# 10AmpBuckV3.net
KiCad netlist of a schematic drawn in EAGLE
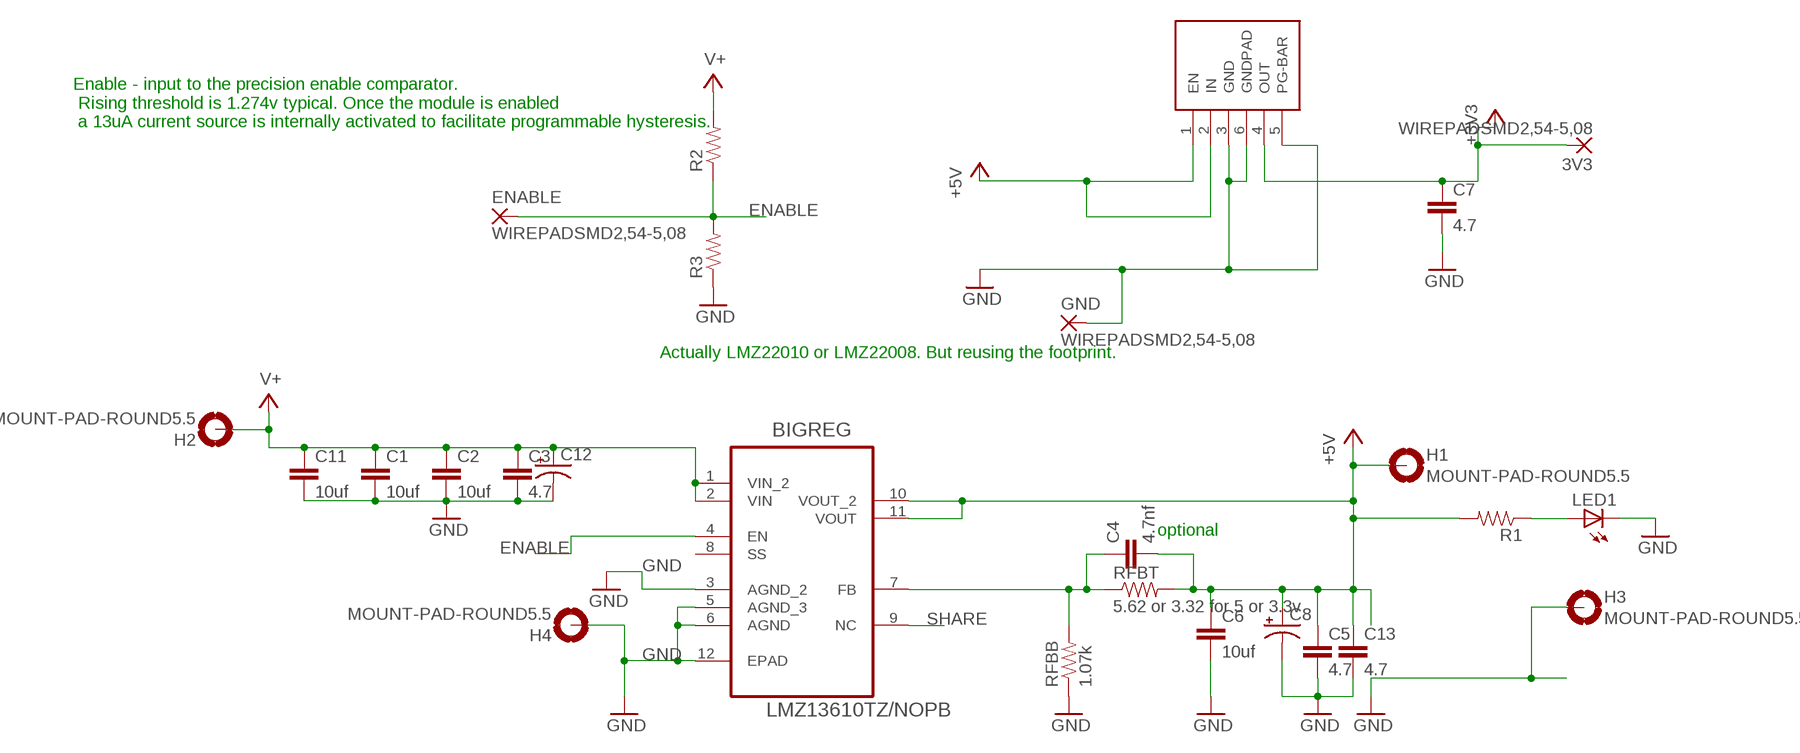
[diagram p0: schematic, sheet 1]

(export (version "E")
  (design (tool "Eeschema 10.0.6"))
  (components
    (comp (ref "3V3")
      (value "WIREPADSMD2,54-5,08")
      (footprint "eagle-import:SMD2,54-5,08")
      (libsource (lib "eagle-import") (part "WIREPADSMD2,54-5,08"))
    )
    (comp (ref "BIGREG")
      (value "LMZ13610TZ/NOPB")
      (footprint "eagle-import:TI_TO-PMOD-11")
      (libsource (lib "eagle-import") (part "LMZ13610TZ/NOPB"))
    )
    (comp (ref "C1")
      (value "10uf")
      (footprint "eagle-import:1206")
      (libsource (lib "eagle-import") (part "CAP1206"))
    )
    (comp (ref "C2")
      (value "10uf")
      (footprint "eagle-import:1206")
      (libsource (lib "eagle-import") (part "CAP1206"))
    )
    (comp (ref "C3")
      (value "4.7")
      (footprint "eagle-import:1206")
      (libsource (lib "eagle-import") (part "CAP1206"))
    )
    (comp (ref "C4")
      (value "4.7nf")
      (footprint "eagle-import:0603-CAP")
      (libsource (lib "eagle-import") (part "SparkFun-Passives_CAP0603-CAP"))
    )
    (comp (ref "C5")
      (value "4.7")
      (footprint "eagle-import:1206")
      (libsource (lib "eagle-import") (part "CAP1206"))
    )
    (comp (ref "C6")
      (value "10uf")
      (footprint "eagle-import:1206")
      (libsource (lib "eagle-import") (part "CAP1206"))
    )
    (comp (ref "C7")
      (value "4.7")
      (footprint "eagle-import:1206")
      (libsource (lib "eagle-import") (part "CAP1206"))
    )
    (comp (ref "C8")
      (value "CAP_POLPTH1")
      (footprint "eagle-import:CPOL-RADIAL-100UF-25V")
      (libsource (lib "eagle-import") (part "CAP_POLPTH1"))
    )
    (comp (ref "C11")
      (value "10uf")
      (footprint "eagle-import:1206")
      (libsource (lib "eagle-import") (part "CAP1206"))
    )
    (comp (ref "C12")
      (value "CAP_POLPTH1")
      (footprint "eagle-import:CPOL-RADIAL-100UF-25V")
      (libsource (lib "eagle-import") (part "CAP_POLPTH1"))
    )
    (comp (ref "C13")
      (value "4.7")
      (footprint "eagle-import:1206")
      (libsource (lib "eagle-import") (part "CAP1206"))
    )
    (comp (ref "ENABLE")
      (value "WIREPADSMD2,54-5,08")
      (footprint "eagle-import:SMD2,54-5,08")
      (libsource (lib "eagle-import") (part "WIREPADSMD2,54-5,08"))
    )
    (comp (ref "GND")
      (value "WIREPADSMD2,54-5,08")
      (footprint "eagle-import:SMD2,54-5,08")
      (libsource (lib "eagle-import") (part "WIREPADSMD2,54-5,08"))
    )
    (comp (ref "H1")
      (value "MOUNT-PAD-ROUND5.5")
      (footprint "eagle-import:5,5-PAD")
      (libsource (lib "eagle-import") (part "MOUNT-PAD-ROUND5.5"))
    )
    (comp (ref "H2")
      (value "MOUNT-PAD-ROUND5.5")
      (footprint "eagle-import:5,5-PAD")
      (libsource (lib "eagle-import") (part "MOUNT-PAD-ROUND5.5"))
    )
    (comp (ref "H3")
      (value "MOUNT-PAD-ROUND5.5")
      (footprint "eagle-import:5,5-PAD")
      (libsource (lib "eagle-import") (part "MOUNT-PAD-ROUND5.5"))
    )
    (comp (ref "H4")
      (value "MOUNT-PAD-ROUND5.5")
      (footprint "eagle-import:5,5-PAD")
      (libsource (lib "eagle-import") (part "MOUNT-PAD-ROUND5.5"))
    )
    (comp (ref "LED1")
      (value "LED1206")
      (footprint "eagle-import:LED-1206")
      (libsource (lib "eagle-import") (part "LED1206"))
    )
    (comp (ref "R1")
      (value "RESISTOR0603-RES")
      (footprint "eagle-import:0603-RES")
      (libsource (lib "eagle-import") (part "RESISTOR0603-RES"))
    )
    (comp (ref "R2")
      (value "RESISTOR0603-RES")
      (footprint "eagle-import:0603-RES")
      (libsource (lib "eagle-import") (part "RESISTOR0603-RES"))
    )
    (comp (ref "R3")
      (value "RESISTOR0603-RES")
      (footprint "eagle-import:0603-RES")
      (libsource (lib "eagle-import") (part "RESISTOR0603-RES"))
    )
    (comp (ref "RFBB")
      (value "1.07k")
      (footprint "eagle-import:0603-RES")
      (libsource (lib "eagle-import") (part "RESISTOR0603"))
    )
    (comp (ref "RFBT")
      (value "5.62 or 3.32 for 5 or 3.3v")
      (footprint "eagle-import:0603-RES")
      (libsource (lib "eagle-import") (part "RESISTOR0603"))
    )
    (comp (ref "U$1")
      (value "TPS75533")
      (footprint "eagle-import:TO263-5")
      (libsource (lib "eagle-import") (part "TPS75533"))
    )
  )
  (nets
    (net (code "1") (name "+3V3") (class "Default")
      (node (ref "3V3") (pin "1") (pinfunction "P_1") (pintype "passive"))
      (node (ref "C7") (pin "1") (pinfunction "1_1") (pintype "passive"))
      (node (ref "U$1") (pin "4") (pinfunction "OUT_4") (pintype "bidirectional"))
    )
    (net (code "2") (name "+5V") (class "Default")
      (node (ref "BIGREG") (pin "10") (pinfunction "VOUT_2_10") (pintype "output"))
      (node (ref "BIGREG") (pin "11") (pinfunction "VOUT_11") (pintype "output"))
      (node (ref "C13") (pin "1") (pinfunction "1_1") (pintype "passive"))
      (node (ref "C4") (pin "2") (pinfunction "2_2") (pintype "passive"))
      (node (ref "C5") (pin "1") (pinfunction "1_1") (pintype "passive"))
      (node (ref "C6") (pin "1") (pinfunction "1_1") (pintype "passive"))
      (node (ref "C8") (pin "1") (pinfunction "+_1") (pintype "passive"))
      (node (ref "H1") (pin "B5,5") (pinfunction "MOUNT_B5,5") (pintype "passive"))
      (node (ref "R1") (pin "2") (pinfunction "2_2") (pintype "passive"))
      (node (ref "RFBT") (pin "2") (pinfunction "2_2") (pintype "passive"))
      (node (ref "U$1") (pin "1") (pinfunction "EN_1") (pintype "bidirectional"))
      (node (ref "U$1") (pin "2") (pinfunction "IN_2") (pintype "bidirectional"))
    )
    (net (code "3") (name "/ENABLE") (class "Default")
      (node (ref "BIGREG") (pin "4") (pinfunction "EN_4") (pintype "input"))
      (node (ref "ENABLE") (pin "1") (pinfunction "P_1") (pintype "passive"))
      (node (ref "R2") (pin "1") (pinfunction "1_1") (pintype "passive"))
      (node (ref "R3") (pin "2") (pinfunction "2_2") (pintype "passive"))
    )
    (net (code "5") (name "GND") (class "Default")
      (node (ref "BIGREG") (pin "12") (pinfunction "EPAD_12") (pintype "passive"))
      (node (ref "BIGREG") (pin "3") (pinfunction "AGND_2_3") (pintype "passive"))
      (node (ref "BIGREG") (pin "5") (pinfunction "AGND_3_5") (pintype "passive"))
      (node (ref "BIGREG") (pin "6") (pinfunction "AGND_6") (pintype "passive"))
      (node (ref "C1") (pin "2") (pinfunction "2_2") (pintype "passive"))
      (node (ref "C11") (pin "2") (pinfunction "2_2") (pintype "passive"))
      (node (ref "C12") (pin "2") (pinfunction "-_2") (pintype "passive"))
      (node (ref "C13") (pin "2") (pinfunction "2_2") (pintype "passive"))
      (node (ref "C2") (pin "2") (pinfunction "2_2") (pintype "passive"))
      (node (ref "C3") (pin "2") (pinfunction "2_2") (pintype "passive"))
      (node (ref "C5") (pin "2") (pinfunction "2_2") (pintype "passive"))
      (node (ref "C6") (pin "2") (pinfunction "2_2") (pintype "passive"))
      (node (ref "C7") (pin "2") (pinfunction "2_2") (pintype "passive"))
      (node (ref "C8") (pin "2") (pinfunction "-_2") (pintype "passive"))
      (node (ref "GND") (pin "1") (pinfunction "P_1") (pintype "passive"))
      (node (ref "H3") (pin "B5,5") (pinfunction "MOUNT_B5,5") (pintype "passive"))
      (node (ref "H4") (pin "B5,5") (pinfunction "MOUNT_B5,5") (pintype "passive"))
      (node (ref "LED1") (pin "C") (pinfunction "C_C") (pintype "passive"))
      (node (ref "R3") (pin "1") (pinfunction "1_1") (pintype "passive"))
      (node (ref "RFBB") (pin "1") (pinfunction "1_1") (pintype "passive"))
      (node (ref "U$1") (pin "3") (pinfunction "GND_3") (pintype "bidirectional"))
      (node (ref "U$1") (pin "5") (pinfunction "PG-BAR_5") (pintype "bidirectional"))
      (node (ref "U$1") (pin "6") (pinfunction "GNDPAD_6") (pintype "bidirectional"))
    )
    (net (code "6") (name "Net-(BIGREG-FB)") (class "Default")
      (node (ref "BIGREG") (pin "7") (pinfunction "FB_7") (pintype "input"))
      (node (ref "C4") (pin "1") (pinfunction "1_1") (pintype "passive"))
      (node (ref "RFBB") (pin "2") (pinfunction "2_2") (pintype "passive"))
      (node (ref "RFBT") (pin "1") (pinfunction "1_1") (pintype "passive"))
    )
    (net (code "7") (name "Net-(LED1-PadA)") (class "Default")
      (node (ref "LED1") (pin "A") (pinfunction "A_A") (pintype "passive"))
      (node (ref "R1") (pin "1") (pinfunction "1_1") (pintype "passive"))
    )
    (net (code "8") (name "V+") (class "Default")
      (node (ref "BIGREG") (pin "1") (pinfunction "VIN_2_1") (pintype "power_in"))
      (node (ref "BIGREG") (pin "2") (pinfunction "VIN_2") (pintype "power_in"))
      (node (ref "C1") (pin "1") (pinfunction "1_1") (pintype "passive"))
      (node (ref "C11") (pin "1") (pinfunction "1_1") (pintype "passive"))
      (node (ref "C12") (pin "1") (pinfunction "+_1") (pintype "passive"))
      (node (ref "C2") (pin "1") (pinfunction "1_1") (pintype "passive"))
      (node (ref "C3") (pin "1") (pinfunction "1_1") (pintype "passive"))
      (node (ref "H2") (pin "B5,5") (pinfunction "MOUNT_B5,5") (pintype "passive"))
      (node (ref "R2") (pin "2") (pinfunction "2_2") (pintype "passive"))
    )
    (net (code "9") (name "unconnected-(BIGREG-NC-Pad9)") (class "Default")
      (node (ref "BIGREG") (pin "9") (pinfunction "NC_9") (pintype "no_connect"))
    )
    (net (code "10") (name "unconnected-(BIGREG-SS-Pad8)") (class "Default")
      (node (ref "BIGREG") (pin "8") (pinfunction "SS_8") (pintype "input"))
    )
  )
)
